# Schematic_diagram.net
KiCad netlist of a schematic drawn in Altium Designer
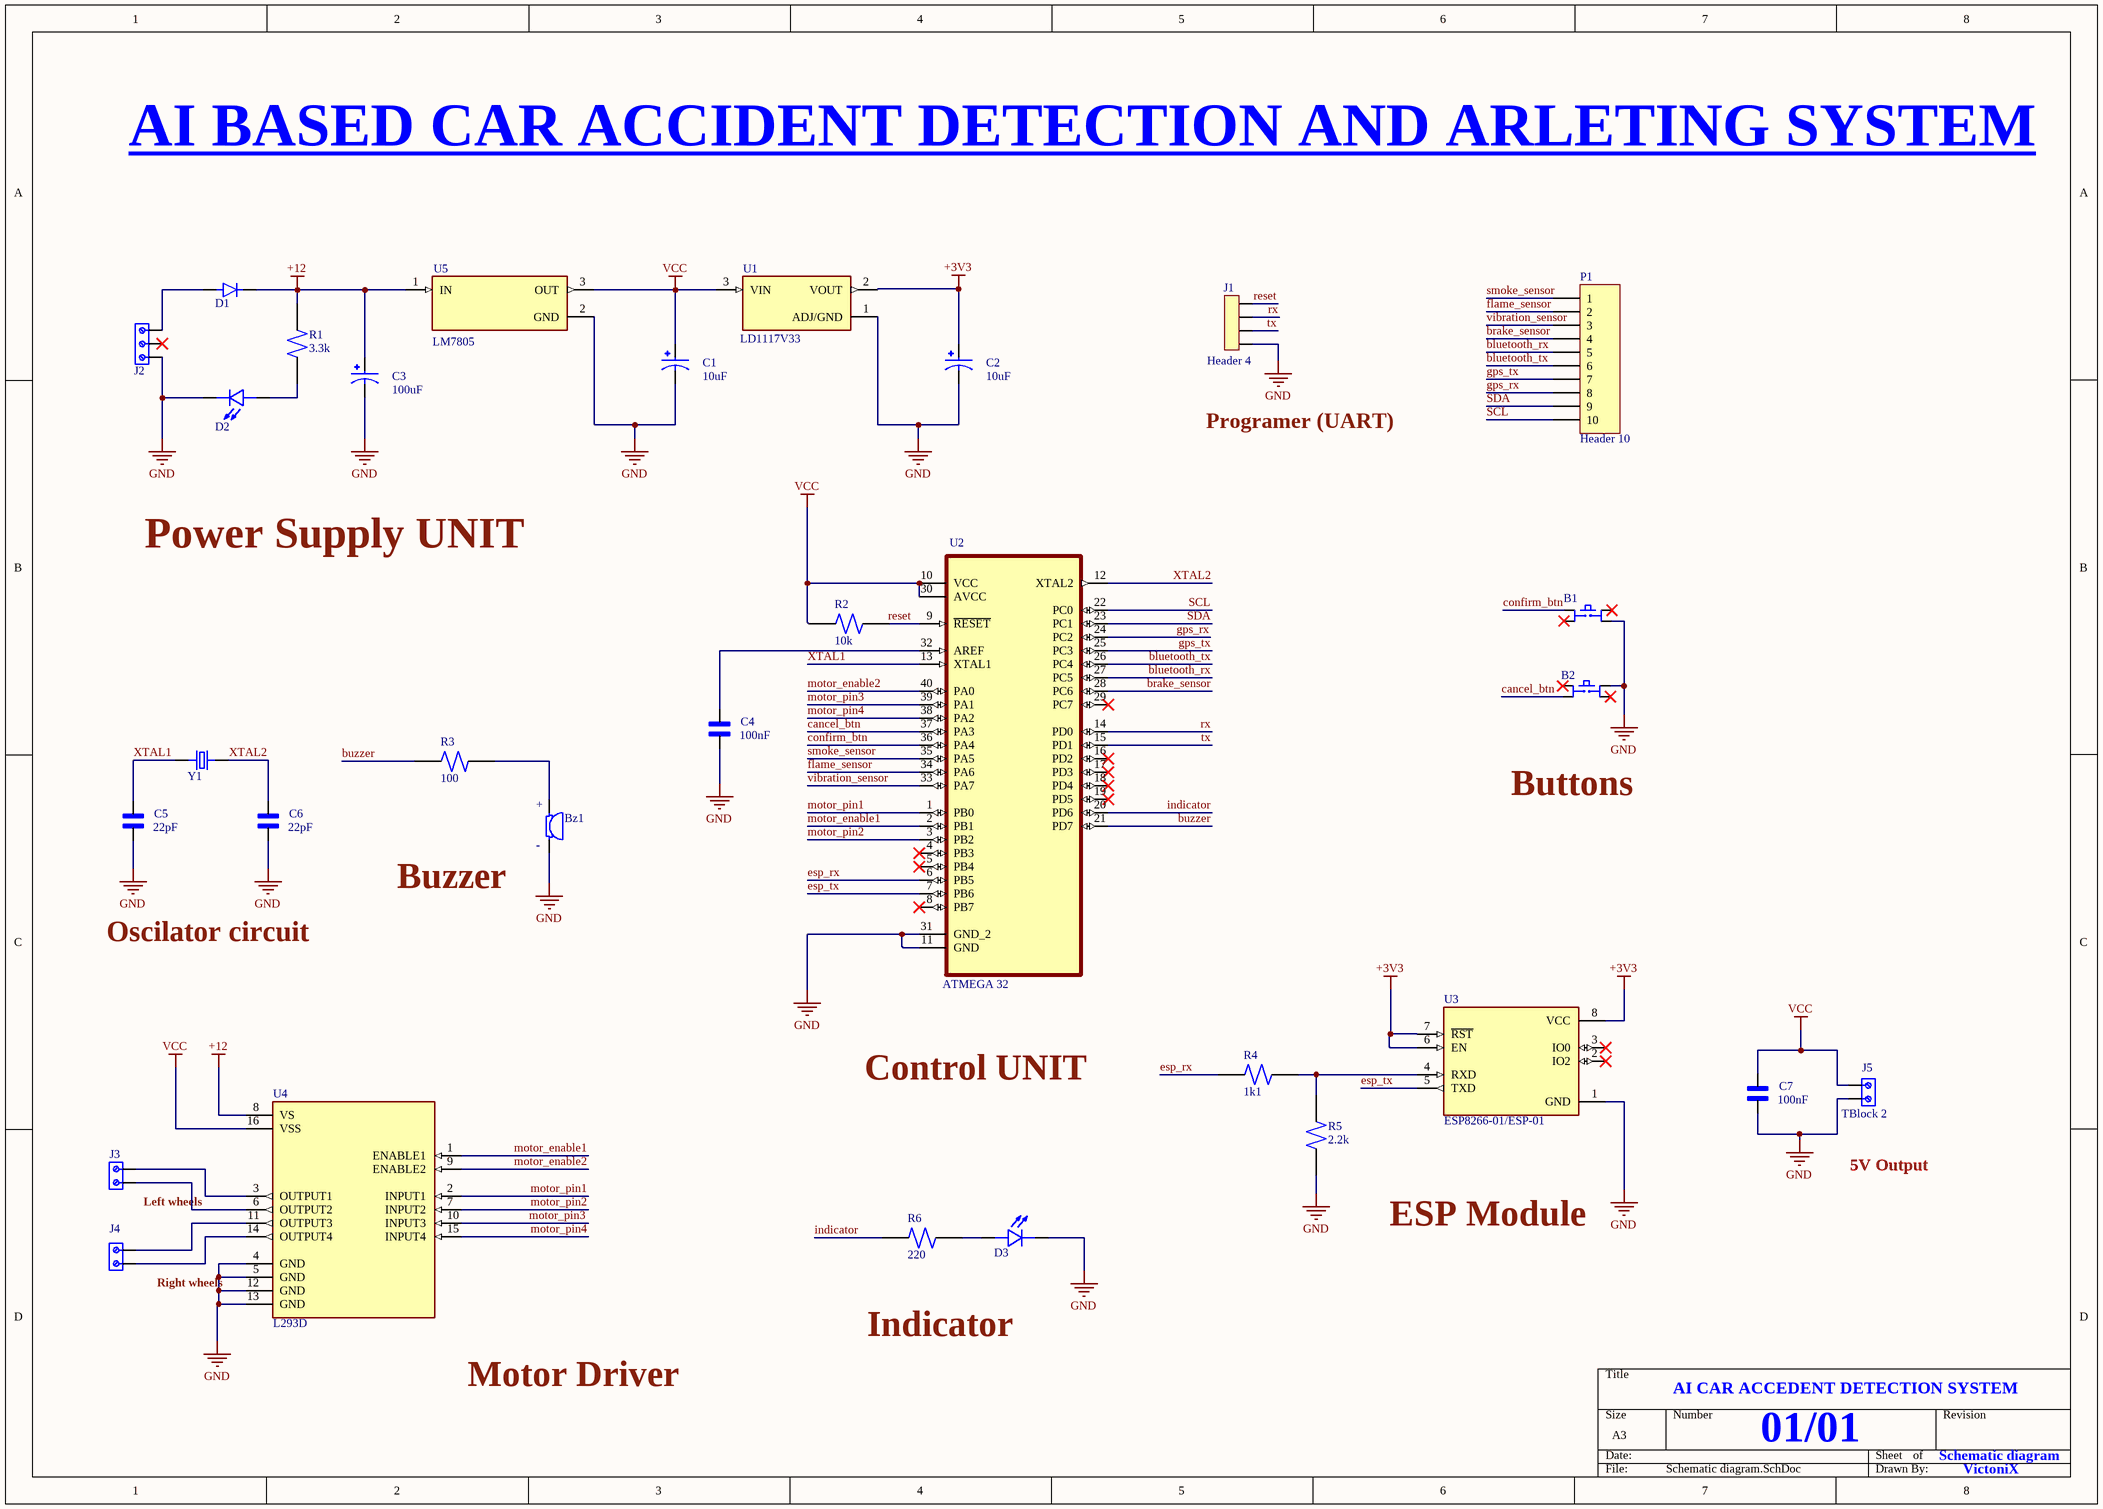
[diagram p0: Schematic diagram.SchDoc]

(export (version "E")
  (design (tool "Eeschema 10.0.6"))
  (components
    (comp (ref "B1")
      (value "Push button")
      (footprint "SW_TS02-66-95-BK-260-LCR-D")
      (libsource (lib "Installed library") (part "Push button"))
    )
    (comp (ref "B2")
      (value "Push button")
      (footprint "SW_TS02-66-95-BK-260-LCR-D")
      (libsource (lib "Installed library") (part "Push button"))
    )
    (comp (ref "Bz1")
      (value "AI-1223-TWT-12V-R")
      (footprint "XDCR_AI-1223-TWT-12V-R")
      (description "ELECTRO-MECHANICAL AUDIO INDICATOR")
      (fields (field (name "MF") "PUI Audio,"))
      (libsource (lib "Installed library") (part "Buzzer"))
    )
    (comp (ref "C1")
      (value "10uF")
      (footprint "CAPPRD500W50D500H1100")
      (description "FS-A")
      (fields (field (name "MF") "{'manufacturer': u'Panasonic'}") (field (name "MP") "EEUFS0J221B"))
      (libsource (lib "Installed library") (part "Electrolytic capacitor"))
    )
    (comp (ref "C2")
      (value "10uF")
      (footprint "CAPPRD500W50D500H1100")
      (description "FS-A")
      (fields (field (name "MF") "{'manufacturer': u'Panasonic'}") (field (name "MP") "EEUFS0J221B"))
      (libsource (lib "Installed library") (part "Electrolytic capacitor"))
    )
    (comp (ref "C3")
      (value "100uF")
      (footprint "CAPPRD500W50D500H1100")
      (description "FS-A")
      (fields (field (name "MF") "{'manufacturer': u'Panasonic'}") (field (name "MP") "EEUFS0J221B"))
      (libsource (lib "Installed library") (part "Electrolytic capacitor"))
    )
    (comp (ref "C4")
      (value "100nF")
      (footprint "CAPRB500W50L450T300H550")
      (description "2200 pF Â±10% 250V Ceramic Capacitor X7R Radial")
      (fields (field (name "DIGI-KEY_PART_NUMBER") "445-173386-1-ND") (field (name "MF") "TDK"))
      (libsource (lib "Installed library") (part "Ceramic capacitor"))
    )
    (comp (ref "C5")
      (value "22pF")
      (footprint "CAPRB500W50L450T300H550")
      (description "2200 pF Â±10% 250V Ceramic Capacitor X7R Radial")
      (fields (field (name "DIGI-KEY_PART_NUMBER") "445-173386-1-ND") (field (name "MF") "TDK"))
      (libsource (lib "Installed library") (part "Ceramic capacitor"))
    )
    (comp (ref "C6")
      (value "22pF")
      (footprint "CAPRB500W50L450T300H550")
      (description "2200 pF Â±10% 250V Ceramic Capacitor X7R Radial")
      (fields (field (name "DIGI-KEY_PART_NUMBER") "445-173386-1-ND") (field (name "MF") "TDK"))
      (libsource (lib "Installed library") (part "Ceramic capacitor"))
    )
    (comp (ref "C7")
      (value "100nF")
      (footprint "CAPRB500W50L450T300H550")
      (description "2200 pF Â±10% 250V Ceramic Capacitor X7R Radial")
      (fields (field (name "DIGI-KEY_PART_NUMBER") "445-173386-1-ND") (field (name "MF") "TDK"))
      (libsource (lib "Installed library") (part "Ceramic capacitor"))
    )
    (comp (ref "D1")
      (value "1N4007")
      (footprint "DIOAD1060W70L435D230")
      (description "Diode Switching 1KV 1A 2-Pin DO-41")
      (libsource (lib "Installed library") (part "Diode"))
    )
    (comp (ref "D2")
      (value "L08R5000Q1")
      (footprint "LEDRD254W57D500H1070")
      (description "LED, Orange, Through Hole, T-1 3/4 (5mm), 30 mA, 2.1 V, 635 nm")
      (fields (field (name "MF") "{'manufacturer': u'LED Technology'}"))
      (libsource (lib "Installed library") (part "LED"))
    )
    (comp (ref "D3")
      (value "L08R5000Q1")
      (footprint "LEDRD254W57D500H1070")
      (description "LED, Orange, Through Hole, T-1 3/4 (5mm), 30 mA, 2.1 V, 635 nm")
      (fields (field (name "MF") "{'manufacturer': u'LED Technology'}"))
      (libsource (lib "Installed library") (part "LED"))
    )
    (comp (ref "J1")
      (value "Header 4")
      (footprint "SULLINS_PPTC041LFBN-RC")
      (description "4 Position Header Connector Through Hole")
      (fields (field (name "MP") "PPTC041LFBN-RC") (field (name "MF") "Sullins Connector"))
      (libsource (lib "Installed library") (part "Female header - 4Pins"))
    )
    (comp (ref "J2")
      (value "691214110003")
      (footprint "691214110003")
      (description "3 Position Wire to Board Terminal Block Horizontal with Board 0.138 (3.50mm) Through Hole")
      (fields (field (name "MF") "Wurth Elektronik"))
      (libsource (lib "Installed library") (part "Terminal blocks - 3Pins (Small)"))
    )
    (comp (ref "J3")
      (value "691111710002")
      (footprint "691111710002")
      (description "2 Position Wire to Board Terminal Block Horizontal with Board 0.197 _5.00mm_ Through Hole")
      (fields (field (name "MF") "Wurth Electronics"))
      (libsource (lib "Installed library") (part "Terminal Block - 2Pins"))
    )
    (comp (ref "J4")
      (value "691111710002")
      (footprint "691111710002")
      (description "2 Position Wire to Board Terminal Block Horizontal with Board 0.197 _5.00mm_ Through Hole")
      (fields (field (name "MF") "Wurth Electronics"))
      (libsource (lib "Installed library") (part "Terminal Block - 2Pins"))
    )
    (comp (ref "J5")
      (value "TBlock 2")
      (footprint "691111710002")
      (description "2 Position Wire to Board Terminal Block Horizontal with Board 0.197 _5.00mm_ Through Hole")
      (fields (field (name "MP") "691111710002") (field (name "MF") "Wurth Electronics"))
      (libsource (lib "Installed library") (part "Terminal Block - 2Pins"))
    )
    (comp (ref "P1")
      (value "Header 10")
      (footprint "HDR1X10")
      (description "Header, 10-Pin")
      (fields (field (name "PUBLISHER") "Altium Limited"))
      (libsource (lib "Miscellaneous Connectors") (part "Header 10"))
    )
    (comp (ref "R1")
      (value "3.3k")
      (footprint "RESAD1100W55L680D260")
      (description "(MFR-25FBF52-10K) 10,2 kOhm bei 1% 0,25W, 1/4W Durchbohrlochwiderstand Axial Metal Film")
      (fields (field (name "DIGI-KEY_PART_NUMBER") "10.2KXBK-ND") (field (name "MF") "Yageo"))
      (libsource (lib "Installed library") (part "Resistor (0.25W)"))
    )
    (comp (ref "R2")
      (value "10k")
      (footprint "RESAD1100W55L680D260")
      (description "(MFR-25FBF52-10K) 10,2 kOhm bei 1% 0,25W, 1/4W Durchbohrlochwiderstand Axial Metal Film")
      (fields (field (name "DIGI-KEY_PART_NUMBER") "10.2KXBK-ND") (field (name "MF") "Yageo"))
      (libsource (lib "Installed library") (part "Resistor (0.25W)"))
    )
    (comp (ref "R3")
      (value "100")
      (footprint "RESAD1100W55L680D260")
      (description "(MFR-25FBF52-10K) 10,2 kOhm bei 1% 0,25W, 1/4W Durchbohrlochwiderstand Axial Metal Film")
      (fields (field (name "DIGI-KEY_PART_NUMBER") "10.2KXBK-ND") (field (name "MF") "Yageo"))
      (libsource (lib "Installed library") (part "Resistor (0.25W)"))
    )
    (comp (ref "R4")
      (value "1k1")
      (footprint "RESAD1100W55L680D260")
      (description "(MFR-25FBF52-10K) 10,2 kOhm bei 1% 0,25W, 1/4W Durchbohrlochwiderstand Axial Metal Film")
      (fields (field (name "DIGI-KEY_PART_NUMBER") "10.2KXBK-ND") (field (name "MF") "Yageo"))
      (libsource (lib "Installed library") (part "Resistor (0.25W)"))
    )
    (comp (ref "R5")
      (value "2.2k")
      (footprint "RESAD1100W55L680D260")
      (description "(MFR-25FBF52-10K) 10,2 kOhm bei 1% 0,25W, 1/4W Durchbohrlochwiderstand Axial Metal Film")
      (fields (field (name "DIGI-KEY_PART_NUMBER") "10.2KXBK-ND") (field (name "MF") "Yageo"))
      (libsource (lib "Installed library") (part "Resistor (0.25W)"))
    )
    (comp (ref "R6")
      (value "220")
      (footprint "RESAD1100W55L680D260")
      (description "(MFR-25FBF52-10K) 10,2 kOhm bei 1% 0,25W, 1/4W Durchbohrlochwiderstand Axial Metal Film")
      (fields (field (name "DIGI-KEY_PART_NUMBER") "10.2KXBK-ND") (field (name "MF") "Yageo"))
      (libsource (lib "Installed library") (part "Resistor (0.25W)"))
    )
    (comp (ref "U1")
      (value "LD1117V33")
      (footprint "TO255P1020X450X1968-3")
      (libsource (lib "Installed library") (part "LD1117V33"))
    )
    (comp (ref "U2")
      (value "ATMEGA 32")
      (footprint "DIP254P1524X482-40")
      (description "AVR AVRÂ® ATmega Microcontroller IC 8-Bit 16MHz 16KB _8K x 16_ FLASH 40-PDIP")
      (fields (field (name "MF") "Microchip") (field (name "MP") "ATMEGA16A-PU"))
      (libsource (lib "Installed library") (part "ATMEGA16A-PU"))
    )
    (comp (ref "U3")
      (value "ESP8266-01/ESP-01")
      (footprint "XCVR_ESP8266-01/ESP-01")
      (libsource (lib "Installed library") (part "ESP8266-01 Module"))
    )
    (comp (ref "U4")
      (value "L293D")
      (footprint "DIP880W50P254L2000H510Q16")
      (description "4-Channel Motor Driver 24V 16-Pin Power PDIP Tube")
      (libsource (lib "Installed library") (part "L293D"))
    )
    (comp (ref "U5")
      (value "LM7805")
      (footprint "TO254P1054X470X1955-3")
      (fields (field (name "MP") "LM7805CT/NOPB"))
      (libsource (lib "Installed library") (part "LM7805"))
    )
    (comp (ref "Y1")
      (value "ECS-160-S-4")
      (footprint "XTAL_ECS-160-20-4X")
      (description "CRYSTAL T/H")
      (fields (field (name "MF") "{'manufacturer': u'ECS Inc.'}"))
      (libsource (lib "Installed library") (part "Crystal oscilator"))
    )
  )
  (nets
    (net (code "1") (name "+3V3") (class "Default")
      (node (ref "C2") (pin "P") (pinfunction "P_P") (pintype "passive"))
      (node (ref "U1") (pin "2") (pinfunction "VOUT_2") (pintype "output"))
      (node (ref "U3") (pin "6") (pinfunction "EN_6") (pintype "input"))
      (node (ref "U3") (pin "7") (pinfunction "~{RST}_7") (pintype "input"))
      (node (ref "U3") (pin "8") (pinfunction "VCC_8") (pintype "power_in"))
    )
    (net (code "2") (name "+12") (class "Default")
      (node (ref "C3") (pin "P") (pinfunction "P_P") (pintype "passive"))
      (node (ref "D1") (pin "C") (pinfunction "C_C") (pintype "passive"))
      (node (ref "R1") (pin "2") (pinfunction "2_2") (pintype "passive"))
      (node (ref "U4") (pin "8") (pinfunction "VS_8") (pintype "power_in"))
      (node (ref "U5") (pin "1") (pinfunction "IN_1") (pintype "input"))
    )
    (net (code "3") (name "/SCL") (class "Default")
      (node (ref "P1") (pin "10") (pinfunction "10_10") (pintype "passive"))
      (node (ref "U2") (pin "22") (pinfunction "PC0_22") (pintype "bidirectional"))
    )
    (net (code "4") (name "/SDA") (class "Default")
      (node (ref "P1") (pin "9") (pinfunction "9_9") (pintype "passive"))
      (node (ref "U2") (pin "23") (pinfunction "PC1_23") (pintype "bidirectional"))
    )
    (net (code "5") (name "/XTAL1") (class "Default")
      (node (ref "C5") (pin "2") (pinfunction "2_2") (pintype "passive"))
      (node (ref "U2") (pin "13") (pinfunction "XTAL1_13") (pintype "input"))
      (node (ref "Y1") (pin "1") (pinfunction "1_1") (pintype "passive"))
    )
    (net (code "6") (name "/XTAL2") (class "Default")
      (node (ref "C6") (pin "2") (pinfunction "2_2") (pintype "passive"))
      (node (ref "U2") (pin "12") (pinfunction "XTAL2_12") (pintype "output"))
      (node (ref "Y1") (pin "2") (pinfunction "2_2") (pintype "passive"))
    )
    (net (code "7") (name "/bluetooth_rx") (class "Default")
      (node (ref "P1") (pin "5") (pinfunction "5_5") (pintype "passive"))
      (node (ref "U2") (pin "27") (pinfunction "PC5_27") (pintype "bidirectional"))
    )
    (net (code "8") (name "/bluetooth_tx") (class "Default")
      (node (ref "P1") (pin "6") (pinfunction "6_6") (pintype "passive"))
      (node (ref "U2") (pin "26") (pinfunction "PC4_26") (pintype "bidirectional"))
    )
    (net (code "9") (name "/brake_sensor") (class "Default")
      (node (ref "P1") (pin "4") (pinfunction "4_4") (pintype "passive"))
      (node (ref "U2") (pin "28") (pinfunction "PC6_28") (pintype "bidirectional"))
    )
    (net (code "10") (name "/buzzer") (class "Default")
      (node (ref "R3") (pin "2") (pinfunction "2_2") (pintype "passive"))
      (node (ref "U2") (pin "21") (pinfunction "PD7_21") (pintype "bidirectional"))
    )
    (net (code "11") (name "/cancel_btn") (class "Default")
      (node (ref "B2") (pin "2") (pinfunction "2_2") (pintype "passive"))
      (node (ref "U2") (pin "37") (pinfunction "PA3_37") (pintype "bidirectional"))
    )
    (net (code "12") (name "/confirm_btn") (class "Default")
      (node (ref "B1") (pin "1") (pinfunction "1_1") (pintype "passive"))
      (node (ref "U2") (pin "36") (pinfunction "PA4_36") (pintype "bidirectional"))
    )
    (net (code "13") (name "/esp_rx") (class "Default")
      (node (ref "R4") (pin "2") (pinfunction "2_2") (pintype "passive"))
      (node (ref "U2") (pin "6") (pinfunction "PB5_6") (pintype "bidirectional"))
    )
    (net (code "14") (name "/esp_tx") (class "Default")
      (node (ref "U2") (pin "7") (pinfunction "PB6_7") (pintype "bidirectional"))
      (node (ref "U3") (pin "5") (pinfunction "TXD_5") (pintype "output"))
    )
    (net (code "15") (name "/flame_sensor") (class "Default")
      (node (ref "P1") (pin "2") (pinfunction "2_2") (pintype "passive"))
      (node (ref "U2") (pin "34") (pinfunction "PA6_34") (pintype "bidirectional"))
    )
    (net (code "16") (name "/gps_rx") (class "Default")
      (node (ref "P1") (pin "8") (pinfunction "8_8") (pintype "passive"))
      (node (ref "U2") (pin "24") (pinfunction "PC2_24") (pintype "bidirectional"))
    )
    (net (code "17") (name "/gps_tx") (class "Default")
      (node (ref "P1") (pin "7") (pinfunction "7_7") (pintype "passive"))
      (node (ref "U2") (pin "25") (pinfunction "PC3_25") (pintype "bidirectional"))
    )
    (net (code "18") (name "/indicator") (class "Default")
      (node (ref "R6") (pin "2") (pinfunction "2_2") (pintype "passive"))
      (node (ref "U2") (pin "20") (pinfunction "PD6_20") (pintype "bidirectional"))
    )
    (net (code "19") (name "/motor_enable1") (class "Default")
      (node (ref "U2") (pin "2") (pinfunction "PB1_2") (pintype "bidirectional"))
      (node (ref "U4") (pin "1") (pinfunction "ENABLE1_1") (pintype "input"))
    )
    (net (code "20") (name "/motor_enable2") (class "Default")
      (node (ref "U2") (pin "40") (pinfunction "PA0_40") (pintype "bidirectional"))
      (node (ref "U4") (pin "9") (pinfunction "ENABLE2_9") (pintype "input"))
    )
    (net (code "21") (name "/motor_pin1") (class "Default")
      (node (ref "U2") (pin "1") (pinfunction "PB0_1") (pintype "bidirectional"))
      (node (ref "U4") (pin "2") (pinfunction "INPUT1_2") (pintype "input"))
    )
    (net (code "22") (name "/motor_pin2") (class "Default")
      (node (ref "U2") (pin "3") (pinfunction "PB2_3") (pintype "bidirectional"))
      (node (ref "U4") (pin "7") (pinfunction "INPUT2_7") (pintype "input"))
    )
    (net (code "23") (name "/motor_pin3") (class "Default")
      (node (ref "U2") (pin "39") (pinfunction "PA1_39") (pintype "bidirectional"))
      (node (ref "U4") (pin "10") (pinfunction "INPUT3_10") (pintype "input"))
    )
    (net (code "24") (name "/motor_pin4") (class "Default")
      (node (ref "U2") (pin "38") (pinfunction "PA2_38") (pintype "bidirectional"))
      (node (ref "U4") (pin "15") (pinfunction "INPUT4_15") (pintype "input"))
    )
    (net (code "25") (name "/reset") (class "Default")
      (node (ref "J1") (pin "1") (pinfunction "1_1") (pintype "passive"))
      (node (ref "R2") (pin "1") (pinfunction "1_1") (pintype "passive"))
      (node (ref "U2") (pin "9") (pinfunction "~{RESET}_9") (pintype "input"))
    )
    (net (code "26") (name "/rx") (class "Default")
      (node (ref "J1") (pin "2") (pinfunction "2_2") (pintype "passive"))
      (node (ref "U2") (pin "14") (pinfunction "PD0_14") (pintype "bidirectional"))
    )
    (net (code "27") (name "/smoke_sensor") (class "Default")
      (node (ref "P1") (pin "1") (pinfunction "1_1") (pintype "passive"))
      (node (ref "U2") (pin "35") (pinfunction "PA5_35") (pintype "bidirectional"))
    )
    (net (code "28") (name "/tx") (class "Default")
      (node (ref "J1") (pin "3") (pinfunction "3_3") (pintype "passive"))
      (node (ref "U2") (pin "15") (pinfunction "PD1_15") (pintype "bidirectional"))
    )
    (net (code "29") (name "/vibration_sensor") (class "Default")
      (node (ref "P1") (pin "3") (pinfunction "3_3") (pintype "passive"))
      (node (ref "U2") (pin "33") (pinfunction "PA7_33") (pintype "bidirectional"))
    )
    (net (code "30") (name "GND") (class "Default")
      (node (ref "B1") (pin "4") (pinfunction "4_4") (pintype "passive"))
      (node (ref "B2") (pin "3") (pinfunction "3_3") (pintype "passive"))
      (node (ref "Bz1") (pin "N") (pinfunction "NEG_N") (pintype "passive"))
      (node (ref "C1") (pin "N") (pinfunction "N_N") (pintype "passive"))
      (node (ref "C2") (pin "N") (pinfunction "N_N") (pintype "passive"))
      (node (ref "C3") (pin "N") (pinfunction "N_N") (pintype "passive"))
      (node (ref "C4") (pin "1") (pinfunction "1_1") (pintype "passive"))
      (node (ref "C5") (pin "1") (pinfunction "1_1") (pintype "passive"))
      (node (ref "C6") (pin "1") (pinfunction "1_1") (pintype "passive"))
      (node (ref "C7") (pin "1") (pinfunction "1_1") (pintype "passive"))
      (node (ref "D2") (pin "C") (pinfunction "C_C") (pintype "passive"))
      (node (ref "D3") (pin "C") (pinfunction "C_C") (pintype "passive"))
      (node (ref "J1") (pin "4") (pinfunction "4_4") (pintype "passive"))
      (node (ref "J2") (pin "1") (pinfunction "1_1") (pintype "passive"))
      (node (ref "J5") (pin "2") (pinfunction "2_2") (pintype "passive"))
      (node (ref "R5") (pin "1") (pinfunction "1_1") (pintype "passive"))
      (node (ref "U1") (pin "1") (pinfunction "ADJ/GND_1") (pintype "passive"))
      (node (ref "U2") (pin "11") (pinfunction "GND_11") (pintype "passive"))
      (node (ref "U2") (pin "31") (pinfunction "GND_2_31") (pintype "passive"))
      (node (ref "U3") (pin "1") (pinfunction "GND_1") (pintype "power_in"))
      (node (ref "U4") (pin "12") (pinfunction "GND_12") (pintype "power_in"))
      (node (ref "U4") (pin "13") (pinfunction "GND_13") (pintype "power_in"))
      (node (ref "U4") (pin "4") (pinfunction "GND_4") (pintype "power_in"))
      (node (ref "U4") (pin "5") (pinfunction "GND_5") (pintype "power_in"))
      (node (ref "U5") (pin "2") (pinfunction "GND_2") (pintype "power_in"))
    )
    (net (code "31") (name "Net-(Bz1-POS)") (class "Default")
      (node (ref "Bz1") (pin "P") (pinfunction "POS_P") (pintype "passive"))
      (node (ref "R3") (pin "1") (pinfunction "1_1") (pintype "passive"))
    )
    (net (code "32") (name "Net-(D1-PadA)") (class "Default")
      (node (ref "D1") (pin "A") (pinfunction "A_A") (pintype "passive"))
      (node (ref "J2") (pin "3") (pinfunction "3_3") (pintype "passive"))
    )
    (net (code "33") (name "Net-(D2-PadA)") (class "Default")
      (node (ref "D2") (pin "A") (pinfunction "A_A") (pintype "passive"))
      (node (ref "R1") (pin "1") (pinfunction "1_1") (pintype "passive"))
    )
    (net (code "34") (name "Net-(D3-PadA)") (class "Default")
      (node (ref "D3") (pin "A") (pinfunction "A_A") (pintype "passive"))
      (node (ref "R6") (pin "1") (pinfunction "1_1") (pintype "passive"))
    )
    (net (code "35") (name "Net-(U2-AREF)") (class "Default")
      (node (ref "C4") (pin "2") (pinfunction "2_2") (pintype "passive"))
      (node (ref "U2") (pin "32") (pinfunction "AREF_32") (pintype "input"))
    )
    (net (code "36") (name "Net-(U3-RXD)") (class "Default")
      (node (ref "R4") (pin "1") (pinfunction "1_1") (pintype "passive"))
      (node (ref "R5") (pin "2") (pinfunction "2_2") (pintype "passive"))
      (node (ref "U3") (pin "4") (pinfunction "RXD_4") (pintype "input"))
    )
    (net (code "37") (name "Net-(U4-OUTPUT1)") (class "Default")
      (node (ref "J3") (pin "1") (pinfunction "1_1") (pintype "passive"))
      (node (ref "U4") (pin "3") (pinfunction "OUTPUT1_3") (pintype "output"))
    )
    (net (code "38") (name "Net-(U4-OUTPUT2)") (class "Default")
      (node (ref "J3") (pin "2") (pinfunction "2_2") (pintype "passive"))
      (node (ref "U4") (pin "6") (pinfunction "OUTPUT2_6") (pintype "output"))
    )
    (net (code "39") (name "Net-(U4-OUTPUT3)") (class "Default")
      (node (ref "J4") (pin "1") (pinfunction "1_1") (pintype "passive"))
      (node (ref "U4") (pin "11") (pinfunction "OUTPUT3_11") (pintype "output"))
    )
    (net (code "40") (name "Net-(U4-OUTPUT4)") (class "Default")
      (node (ref "J4") (pin "2") (pinfunction "2_2") (pintype "passive"))
      (node (ref "U4") (pin "14") (pinfunction "OUTPUT4_14") (pintype "output"))
    )
    (net (code "41") (name "VCC") (class "Default")
      (node (ref "C1") (pin "P") (pinfunction "P_P") (pintype "passive"))
      (node (ref "C7") (pin "2") (pinfunction "2_2") (pintype "passive"))
      (node (ref "J5") (pin "1") (pinfunction "1_1") (pintype "passive"))
      (node (ref "R2") (pin "2") (pinfunction "2_2") (pintype "passive"))
      (node (ref "U1") (pin "3") (pinfunction "VIN_3") (pintype "input"))
      (node (ref "U2") (pin "10") (pinfunction "VCC_10") (pintype "power_in"))
      (node (ref "U2") (pin "30") (pinfunction "AVCC_30") (pintype "power_in"))
      (node (ref "U4") (pin "16") (pinfunction "VSS_16") (pintype "power_in"))
      (node (ref "U5") (pin "3") (pinfunction "OUT_3") (pintype "output"))
    )
    (net (code "42") (name "unconnected-(B1-Pad2)") (class "Default")
      (node (ref "B1") (pin "2") (pinfunction "2_2") (pintype "passive+no_connect"))
    )
    (net (code "43") (name "unconnected-(B1-Pad3)") (class "Default")
      (node (ref "B1") (pin "3") (pinfunction "3_3") (pintype "passive+no_connect"))
    )
    (net (code "44") (name "unconnected-(B2-Pad1)") (class "Default")
      (node (ref "B2") (pin "1") (pinfunction "1_1") (pintype "passive+no_connect"))
    )
    (net (code "45") (name "unconnected-(B2-Pad4)") (class "Default")
      (node (ref "B2") (pin "4") (pinfunction "4_4") (pintype "passive+no_connect"))
    )
    (net (code "46") (name "unconnected-(J2-Pad2)") (class "Default")
      (node (ref "J2") (pin "2") (pinfunction "2_2") (pintype "passive+no_connect"))
    )
    (net (code "47") (name "unconnected-(U2-PB3-Pad4)") (class "Default")
      (node (ref "U2") (pin "4") (pinfunction "PB3_4") (pintype "bidirectional+no_connect"))
    )
    (net (code "48") (name "unconnected-(U2-PB4-Pad5)") (class "Default")
      (node (ref "U2") (pin "5") (pinfunction "PB4_5") (pintype "bidirectional+no_connect"))
    )
    (net (code "49") (name "unconnected-(U2-PB7-Pad8)") (class "Default")
      (node (ref "U2") (pin "8") (pinfunction "PB7_8") (pintype "bidirectional+no_connect"))
    )
    (net (code "50") (name "unconnected-(U2-PC7-Pad29)") (class "Default")
      (node (ref "U2") (pin "29") (pinfunction "PC7_29") (pintype "bidirectional+no_connect"))
    )
    (net (code "51") (name "unconnected-(U2-PD2-Pad16)") (class "Default")
      (node (ref "U2") (pin "16") (pinfunction "PD2_16") (pintype "bidirectional+no_connect"))
    )
    (net (code "52") (name "unconnected-(U2-PD3-Pad17)") (class "Default")
      (node (ref "U2") (pin "17") (pinfunction "PD3_17") (pintype "bidirectional+no_connect"))
    )
    (net (code "53") (name "unconnected-(U2-PD4-Pad18)") (class "Default")
      (node (ref "U2") (pin "18") (pinfunction "PD4_18") (pintype "bidirectional+no_connect"))
    )
    (net (code "54") (name "unconnected-(U2-PD5-Pad19)") (class "Default")
      (node (ref "U2") (pin "19") (pinfunction "PD5_19") (pintype "bidirectional+no_connect"))
    )
    (net (code "55") (name "unconnected-(U3-IO0-Pad3)") (class "Default")
      (node (ref "U3") (pin "3") (pinfunction "IO0_3") (pintype "bidirectional+no_connect"))
    )
    (net (code "56") (name "unconnected-(U3-IO2-Pad2)") (class "Default")
      (node (ref "U3") (pin "2") (pinfunction "IO2_2") (pintype "bidirectional+no_connect"))
    )
  )
)
